# THS4524_Fully_Diff.net
KiCad netlist of a schematic drawn in Altium Designer
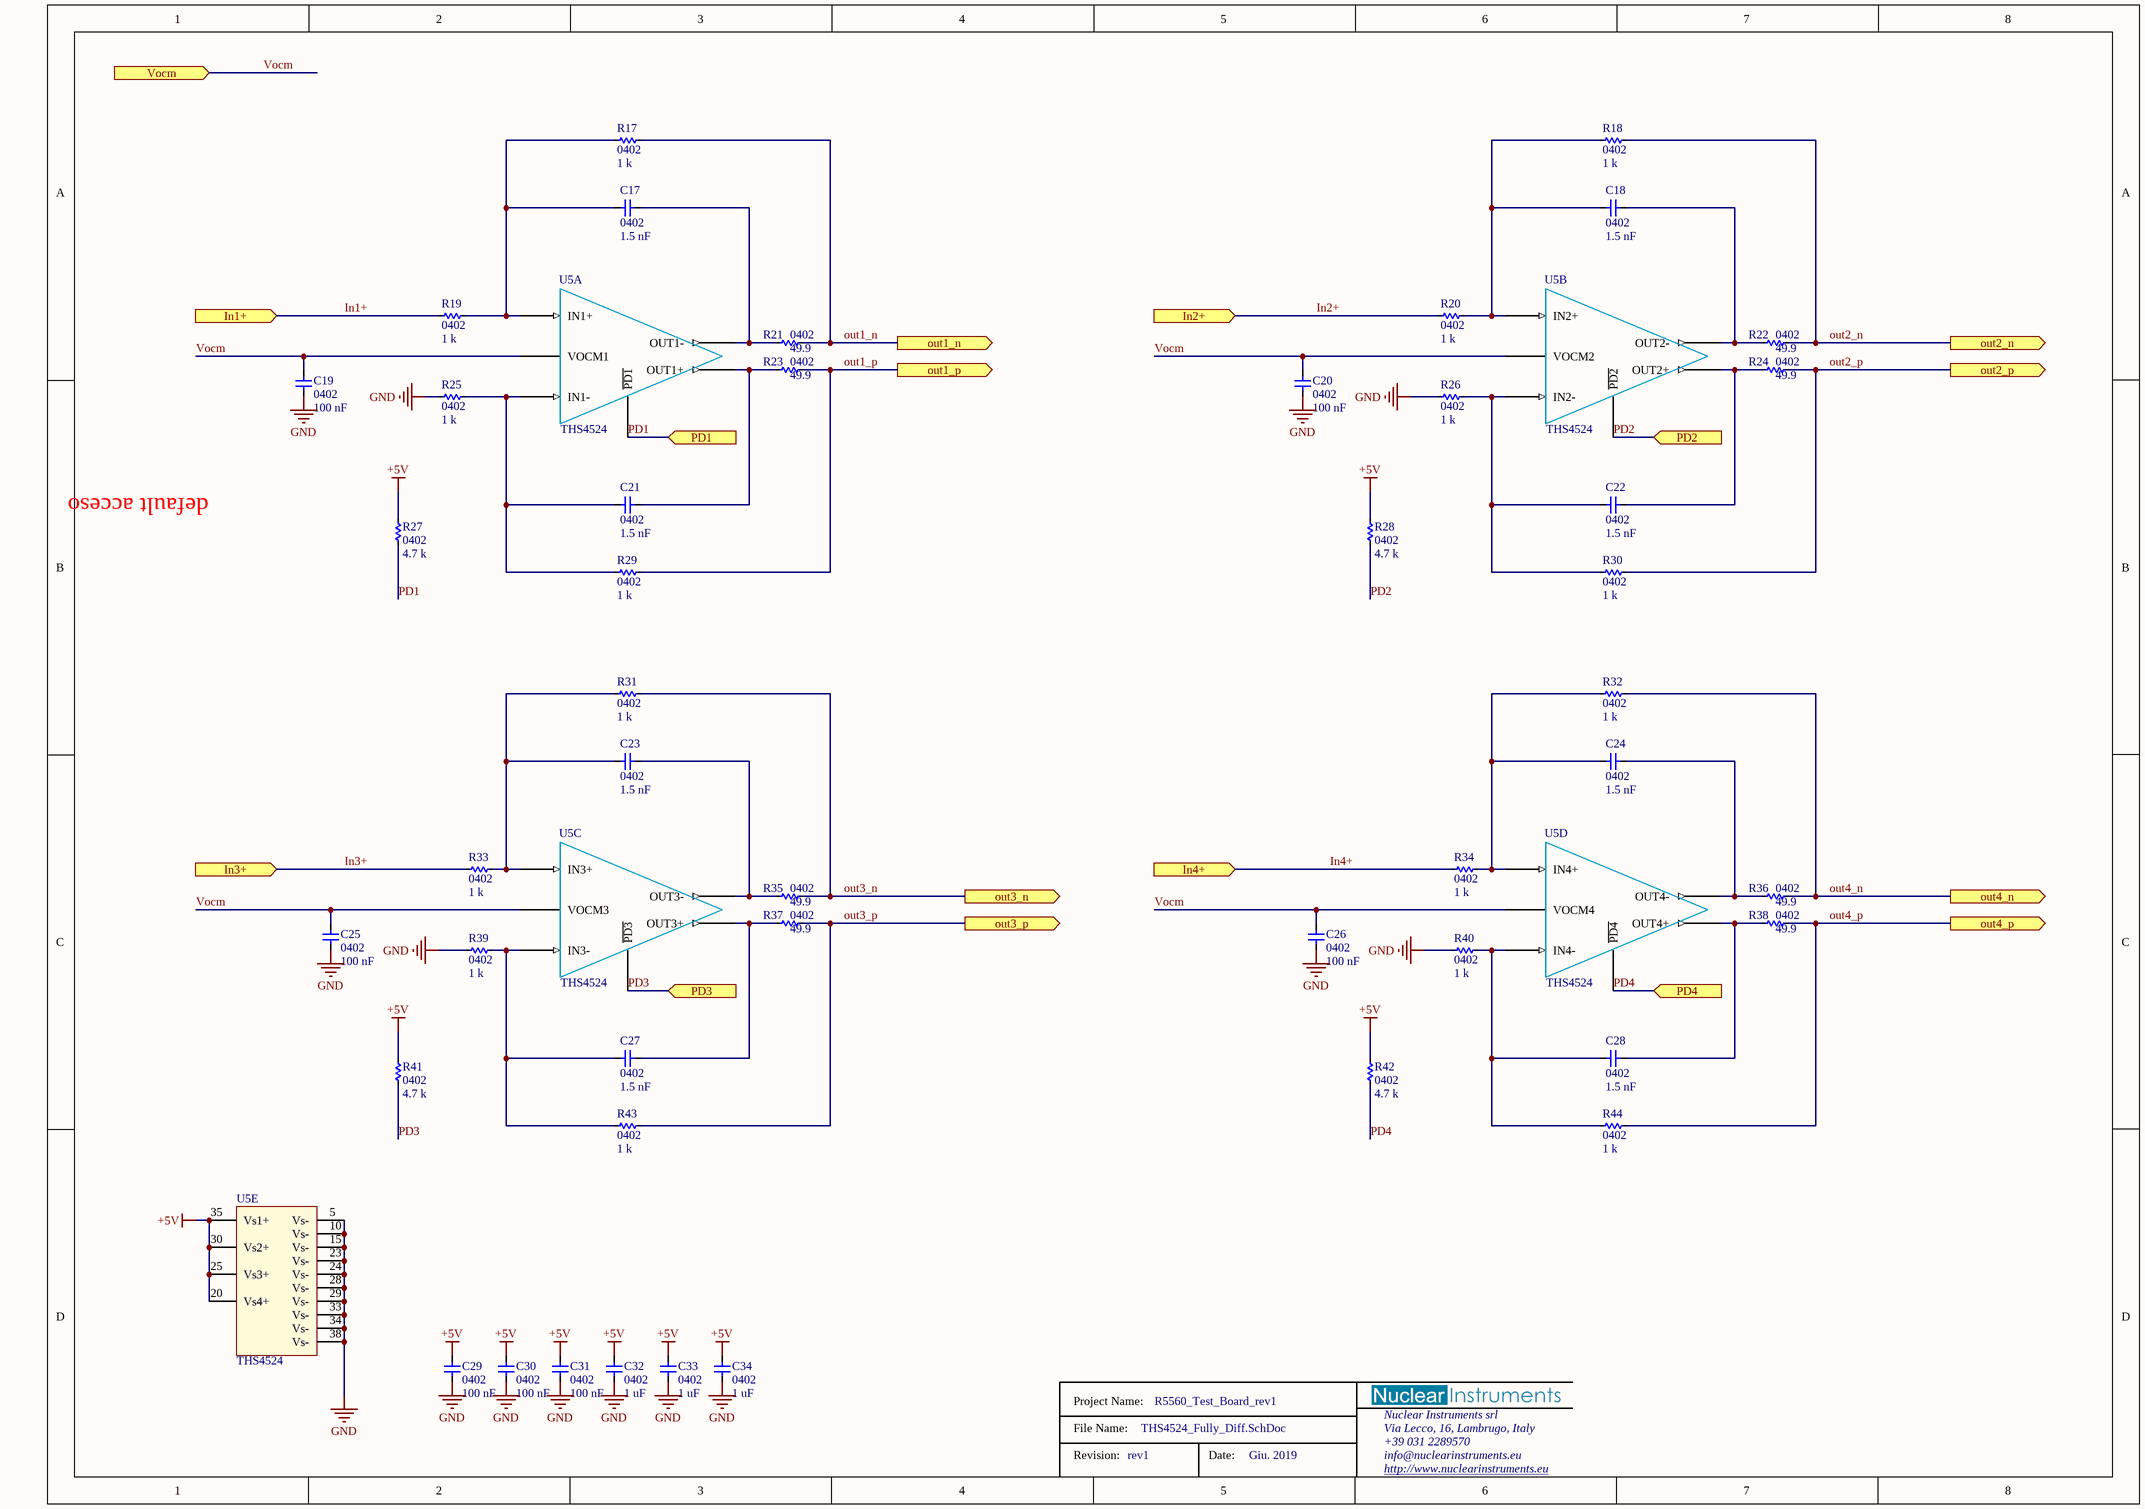
[diagram p0: THS4524_Fully_Diff.SchDoc]

(export (version "E")
  (design (tool "Eeschema 10.0.6"))
  (components
    (comp (ref "C17")
      (value "0402")
      (footprint "CAPCERSMD0402")
      (fields (field (name "ALTIUM_VALUE") "1.5 nF"))
      (libsource (lib "0402_Cap_Cer__SARAversion-23") (part "CAPCER0402_X7R_50V_1n5"))
    )
    (comp (ref "C18")
      (value "0402")
      (footprint "CAPCERSMD0402")
      (fields (field (name "ALTIUM_VALUE") "1.5 nF"))
      (libsource (lib "0402_Cap_Cer__SARAversion-23") (part "CAPCER0402_X7R_50V_1n5"))
    )
    (comp (ref "C19")
      (value "0402")
      (footprint "CAPCERSMD0402")
      (fields (field (name "ALTIUM_VALUE") "100 nF"))
      (libsource (lib "0402_Cap_Cer__SARAversion-23") (part "CAPCER0402_X7R_50V_100n"))
    )
    (comp (ref "C20")
      (value "0402")
      (footprint "CAPCERSMD0402")
      (fields (field (name "ALTIUM_VALUE") "100 nF"))
      (libsource (lib "0402_Cap_Cer__SARAversion-23") (part "CAPCER0402_X7R_50V_100n"))
    )
    (comp (ref "C21")
      (value "0402")
      (footprint "CAPCERSMD0402")
      (fields (field (name "ALTIUM_VALUE") "1.5 nF"))
      (libsource (lib "0402_Cap_Cer__SARAversion-23") (part "CAPCER0402_X7R_50V_1n5"))
    )
    (comp (ref "C22")
      (value "0402")
      (footprint "CAPCERSMD0402")
      (fields (field (name "ALTIUM_VALUE") "1.5 nF"))
      (libsource (lib "0402_Cap_Cer__SARAversion-23") (part "CAPCER0402_X7R_50V_1n5"))
    )
    (comp (ref "C23")
      (value "0402")
      (footprint "CAPCERSMD0402")
      (fields (field (name "ALTIUM_VALUE") "1.5 nF"))
      (libsource (lib "0402_Cap_Cer__SARAversion-23") (part "CAPCER0402_X7R_50V_1n5"))
    )
    (comp (ref "C24")
      (value "0402")
      (footprint "CAPCERSMD0402")
      (fields (field (name "ALTIUM_VALUE") "1.5 nF"))
      (libsource (lib "0402_Cap_Cer__SARAversion-23") (part "CAPCER0402_X7R_50V_1n5"))
    )
    (comp (ref "C25")
      (value "0402")
      (footprint "CAPCERSMD0402")
      (fields (field (name "ALTIUM_VALUE") "100 nF"))
      (libsource (lib "0402_Cap_Cer__SARAversion-23") (part "CAPCER0402_X7R_50V_100n"))
    )
    (comp (ref "C26")
      (value "0402")
      (footprint "CAPCERSMD0402")
      (fields (field (name "ALTIUM_VALUE") "100 nF"))
      (libsource (lib "0402_Cap_Cer__SARAversion-23") (part "CAPCER0402_X7R_50V_100n"))
    )
    (comp (ref "C27")
      (value "0402")
      (footprint "CAPCERSMD0402")
      (fields (field (name "ALTIUM_VALUE") "1.5 nF"))
      (libsource (lib "0402_Cap_Cer__SARAversion-23") (part "CAPCER0402_X7R_50V_1n5"))
    )
    (comp (ref "C28")
      (value "0402")
      (footprint "CAPCERSMD0402")
      (fields (field (name "ALTIUM_VALUE") "1.5 nF"))
      (libsource (lib "0402_Cap_Cer__SARAversion-23") (part "CAPCER0402_X7R_50V_1n5"))
    )
    (comp (ref "C29")
      (value "0402")
      (footprint "CAPCERSMD0402")
      (fields (field (name "ALTIUM_VALUE") "100 nF"))
      (libsource (lib "0402_Cap_Cer__SARAversion-23") (part "CAPCER0402_X7R_50V_100n"))
    )
    (comp (ref "C30")
      (value "0402")
      (footprint "CAPCERSMD0402")
      (fields (field (name "ALTIUM_VALUE") "100 nF"))
      (libsource (lib "0402_Cap_Cer__SARAversion-23") (part "CAPCER0402_X7R_50V_100n"))
    )
    (comp (ref "C31")
      (value "0402")
      (footprint "CAPCERSMD0402")
      (fields (field (name "ALTIUM_VALUE") "100 nF"))
      (libsource (lib "0402_Cap_Cer__SARAversion-23") (part "CAPCER0402_X7R_50V_100n"))
    )
    (comp (ref "C32")
      (value "0402")
      (footprint "CAPCERSMD0402")
      (fields (field (name "ALTIUM_VALUE") "1 uF"))
      (libsource (lib "0402_Cap_Cer__SARAversion-23") (part "CAPCER0402_X5R_10V_1u"))
    )
    (comp (ref "C33")
      (value "0402")
      (footprint "CAPCERSMD0402")
      (fields (field (name "ALTIUM_VALUE") "1 uF"))
      (libsource (lib "0402_Cap_Cer__SARAversion-23") (part "CAPCER0402_X5R_10V_1u"))
    )
    (comp (ref "C34")
      (value "0402")
      (footprint "CAPCERSMD0402")
      (fields (field (name "ALTIUM_VALUE") "1 uF"))
      (libsource (lib "0402_Cap_Cer__SARAversion-23") (part "CAPCER0402_X5R_10V_1u"))
    )
    (comp (ref "R17")
      (value "0402")
      (footprint "RESSMD0402")
      (fields (field (name "ALTIUM_VALUE") "1 k"))
      (libsource (lib "0402_Resistors__SARAversion-52") (part "RES0402-1k"))
    )
    (comp (ref "R18")
      (value "0402")
      (footprint "RESSMD0402")
      (fields (field (name "ALTIUM_VALUE") "1 k"))
      (libsource (lib "0402_Resistors__SARAversion-52") (part "RES0402-1k"))
    )
    (comp (ref "R19")
      (value "0402")
      (footprint "RESSMD0402")
      (fields (field (name "ALTIUM_VALUE") "1 k"))
      (libsource (lib "0402_Resistors__SARAversion-52") (part "RES0402-1k"))
    )
    (comp (ref "R20")
      (value "0402")
      (footprint "RESSMD0402")
      (fields (field (name "ALTIUM_VALUE") "1 k"))
      (libsource (lib "0402_Resistors__SARAversion-52") (part "RES0402-1k"))
    )
    (comp (ref "R21")
      (value "0402")
      (footprint "RESSMD0402")
      (fields (field (name "ALTIUM_VALUE") "49.9"))
      (libsource (lib "0402_Resistors__SARAversion-52") (part "RES0402-49R9"))
    )
    (comp (ref "R22")
      (value "0402")
      (footprint "RESSMD0402")
      (fields (field (name "ALTIUM_VALUE") "49.9"))
      (libsource (lib "0402_Resistors__SARAversion-52") (part "RES0402-49R9"))
    )
    (comp (ref "R23")
      (value "0402")
      (footprint "RESSMD0402")
      (fields (field (name "ALTIUM_VALUE") "49.9"))
      (libsource (lib "0402_Resistors__SARAversion-52") (part "RES0402-49R9"))
    )
    (comp (ref "R24")
      (value "0402")
      (footprint "RESSMD0402")
      (fields (field (name "ALTIUM_VALUE") "49.9"))
      (libsource (lib "0402_Resistors__SARAversion-52") (part "RES0402-49R9"))
    )
    (comp (ref "R25")
      (value "0402")
      (footprint "RESSMD0402")
      (fields (field (name "ALTIUM_VALUE") "1 k"))
      (libsource (lib "0402_Resistors__SARAversion-52") (part "RES0402-1k"))
    )
    (comp (ref "R26")
      (value "0402")
      (footprint "RESSMD0402")
      (fields (field (name "ALTIUM_VALUE") "1 k"))
      (libsource (lib "0402_Resistors__SARAversion-52") (part "RES0402-1k"))
    )
    (comp (ref "R27")
      (value "0402")
      (footprint "RESSMD0402")
      (fields (field (name "ALTIUM_VALUE") "4.7 k"))
      (libsource (lib "0402_Resistors__SARAversion-52") (part "RES0402-4k7"))
    )
    (comp (ref "R28")
      (value "0402")
      (footprint "RESSMD0402")
      (fields (field (name "ALTIUM_VALUE") "4.7 k"))
      (libsource (lib "0402_Resistors__SARAversion-52") (part "RES0402-4k7"))
    )
    (comp (ref "R29")
      (value "0402")
      (footprint "RESSMD0402")
      (fields (field (name "ALTIUM_VALUE") "1 k"))
      (libsource (lib "0402_Resistors__SARAversion-52") (part "RES0402-1k"))
    )
    (comp (ref "R30")
      (value "0402")
      (footprint "RESSMD0402")
      (fields (field (name "ALTIUM_VALUE") "1 k"))
      (libsource (lib "0402_Resistors__SARAversion-52") (part "RES0402-1k"))
    )
    (comp (ref "R31")
      (value "0402")
      (footprint "RESSMD0402")
      (fields (field (name "ALTIUM_VALUE") "1 k"))
      (libsource (lib "0402_Resistors__SARAversion-52") (part "RES0402-1k"))
    )
    (comp (ref "R32")
      (value "0402")
      (footprint "RESSMD0402")
      (fields (field (name "ALTIUM_VALUE") "1 k"))
      (libsource (lib "0402_Resistors__SARAversion-52") (part "RES0402-1k"))
    )
    (comp (ref "R33")
      (value "0402")
      (footprint "RESSMD0402")
      (fields (field (name "ALTIUM_VALUE") "1 k"))
      (libsource (lib "0402_Resistors__SARAversion-52") (part "RES0402-1k"))
    )
    (comp (ref "R34")
      (value "0402")
      (footprint "RESSMD0402")
      (fields (field (name "ALTIUM_VALUE") "1 k"))
      (libsource (lib "0402_Resistors__SARAversion-52") (part "RES0402-1k"))
    )
    (comp (ref "R35")
      (value "0402")
      (footprint "RESSMD0402")
      (fields (field (name "ALTIUM_VALUE") "49.9"))
      (libsource (lib "0402_Resistors__SARAversion-52") (part "RES0402-49R9"))
    )
    (comp (ref "R36")
      (value "0402")
      (footprint "RESSMD0402")
      (fields (field (name "ALTIUM_VALUE") "49.9"))
      (libsource (lib "0402_Resistors__SARAversion-52") (part "RES0402-49R9"))
    )
    (comp (ref "R37")
      (value "0402")
      (footprint "RESSMD0402")
      (fields (field (name "ALTIUM_VALUE") "49.9"))
      (libsource (lib "0402_Resistors__SARAversion-52") (part "RES0402-49R9"))
    )
    (comp (ref "R38")
      (value "0402")
      (footprint "RESSMD0402")
      (fields (field (name "ALTIUM_VALUE") "49.9"))
      (libsource (lib "0402_Resistors__SARAversion-52") (part "RES0402-49R9"))
    )
    (comp (ref "R39")
      (value "0402")
      (footprint "RESSMD0402")
      (fields (field (name "ALTIUM_VALUE") "1 k"))
      (libsource (lib "0402_Resistors__SARAversion-52") (part "RES0402-1k"))
    )
    (comp (ref "R40")
      (value "0402")
      (footprint "RESSMD0402")
      (fields (field (name "ALTIUM_VALUE") "1 k"))
      (libsource (lib "0402_Resistors__SARAversion-52") (part "RES0402-1k"))
    )
    (comp (ref "R41")
      (value "0402")
      (footprint "RESSMD0402")
      (fields (field (name "ALTIUM_VALUE") "4.7 k"))
      (libsource (lib "0402_Resistors__SARAversion-52") (part "RES0402-4k7"))
    )
    (comp (ref "R42")
      (value "0402")
      (footprint "RESSMD0402")
      (fields (field (name "ALTIUM_VALUE") "4.7 k"))
      (libsource (lib "0402_Resistors__SARAversion-52") (part "RES0402-4k7"))
    )
    (comp (ref "R43")
      (value "0402")
      (footprint "RESSMD0402")
      (fields (field (name "ALTIUM_VALUE") "1 k"))
      (libsource (lib "0402_Resistors__SARAversion-52") (part "RES0402-1k"))
    )
    (comp (ref "R44")
      (value "0402")
      (footprint "RESSMD0402")
      (fields (field (name "ALTIUM_VALUE") "1 k"))
      (libsource (lib "0402_Resistors__SARAversion-52") (part "RES0402-1k"))
    )
    (comp (ref "U5")
      (value "THS4524")
      (footprint "SOP38_P50W640L970H120")
      (libsource (lib "Fully_Differential__SARAversion-6") (part "THS4524IDBTR"))
    )
  )
  (nets
    (net (code "1") (name "+5V") (class "Default")
      (node (ref "C29") (pin "2") (pinfunction "2_2") (pintype "passive"))
      (node (ref "C30") (pin "2") (pinfunction "2_2") (pintype "passive"))
      (node (ref "C31") (pin "2") (pinfunction "2_2") (pintype "passive"))
      (node (ref "C32") (pin "2") (pinfunction "2_2") (pintype "passive"))
      (node (ref "C33") (pin "2") (pinfunction "2_2") (pintype "passive"))
      (node (ref "C34") (pin "2") (pinfunction "2_2") (pintype "passive"))
      (node (ref "R27") (pin "1") (pinfunction "1_1") (pintype "passive"))
      (node (ref "R28") (pin "1") (pinfunction "1_1") (pintype "passive"))
      (node (ref "R41") (pin "1") (pinfunction "1_1") (pintype "passive"))
      (node (ref "R42") (pin "1") (pinfunction "1_1") (pintype "passive"))
      (node (ref "U5") (pin "20") (pinfunction "Vs4+_20") (pintype "passive"))
      (node (ref "U5") (pin "25") (pinfunction "Vs3+_25") (pintype "passive"))
      (node (ref "U5") (pin "30") (pinfunction "Vs2+_30") (pintype "passive"))
      (node (ref "U5") (pin "35") (pinfunction "Vs1+_35") (pintype "passive"))
    )
    (net (code "2") (name "/In1+") (class "Default")
      (node (ref "R19") (pin "1") (pinfunction "1_1") (pintype "passive"))
    )
    (net (code "3") (name "/In2+") (class "Default")
      (node (ref "R20") (pin "1") (pinfunction "1_1") (pintype "passive"))
    )
    (net (code "4") (name "/In3+") (class "Default")
      (node (ref "R33") (pin "1") (pinfunction "1_1") (pintype "passive"))
    )
    (net (code "5") (name "/In4+") (class "Default")
      (node (ref "R34") (pin "1") (pinfunction "1_1") (pintype "passive"))
    )
    (net (code "6") (name "/PD1") (class "Default")
      (node (ref "R27") (pin "2") (pinfunction "2_2") (pintype "passive"))
      (node (ref "U5") (pin "1") (pinfunction "~{PD1}_1") (pintype "passive"))
    )
    (net (code "7") (name "/PD2") (class "Default")
      (node (ref "R28") (pin "2") (pinfunction "2_2") (pintype "passive"))
      (node (ref "U5") (pin "6") (pinfunction "~{PD2}_6") (pintype "passive"))
    )
    (net (code "8") (name "/PD3") (class "Default")
      (node (ref "R41") (pin "2") (pinfunction "2_2") (pintype "passive"))
      (node (ref "U5") (pin "11") (pinfunction "~{PD3}_11") (pintype "passive"))
    )
    (net (code "9") (name "/PD4") (class "Default")
      (node (ref "R42") (pin "2") (pinfunction "2_2") (pintype "passive"))
      (node (ref "U5") (pin "16") (pinfunction "~{PD4}_16") (pintype "passive"))
    )
    (net (code "10") (name "/Vocm") (class "Default")
      (node (ref "C19") (pin "2") (pinfunction "2_2") (pintype "passive"))
      (node (ref "C20") (pin "2") (pinfunction "2_2") (pintype "passive"))
      (node (ref "C25") (pin "2") (pinfunction "2_2") (pintype "passive"))
      (node (ref "C26") (pin "2") (pinfunction "2_2") (pintype "passive"))
      (node (ref "U5") (pin "14") (pinfunction "VOCM3_14") (pintype "passive"))
      (node (ref "U5") (pin "19") (pinfunction "VOCM4_19") (pintype "passive"))
      (node (ref "U5") (pin "4") (pinfunction "VOCM1_4") (pintype "passive"))
      (node (ref "U5") (pin "9") (pinfunction "VOCM2_9") (pintype "passive"))
    )
    (net (code "11") (name "/out1_n") (class "Default")
      (node (ref "R17") (pin "2") (pinfunction "2_2") (pintype "passive"))
      (node (ref "R21") (pin "2") (pinfunction "2_2") (pintype "passive"))
    )
    (net (code "12") (name "/out1_p") (class "Default")
      (node (ref "R23") (pin "2") (pinfunction "2_2") (pintype "passive"))
      (node (ref "R29") (pin "2") (pinfunction "2_2") (pintype "passive"))
    )
    (net (code "13") (name "/out2_n") (class "Default")
      (node (ref "R18") (pin "2") (pinfunction "2_2") (pintype "passive"))
      (node (ref "R22") (pin "2") (pinfunction "2_2") (pintype "passive"))
    )
    (net (code "14") (name "/out2_p") (class "Default")
      (node (ref "R24") (pin "2") (pinfunction "2_2") (pintype "passive"))
      (node (ref "R30") (pin "2") (pinfunction "2_2") (pintype "passive"))
    )
    (net (code "15") (name "/out3_n") (class "Default")
      (node (ref "R31") (pin "2") (pinfunction "2_2") (pintype "passive"))
      (node (ref "R35") (pin "2") (pinfunction "2_2") (pintype "passive"))
    )
    (net (code "16") (name "/out3_p") (class "Default")
      (node (ref "R37") (pin "2") (pinfunction "2_2") (pintype "passive"))
      (node (ref "R43") (pin "2") (pinfunction "2_2") (pintype "passive"))
    )
    (net (code "17") (name "/out4_n") (class "Default")
      (node (ref "R32") (pin "2") (pinfunction "2_2") (pintype "passive"))
      (node (ref "R36") (pin "2") (pinfunction "2_2") (pintype "passive"))
    )
    (net (code "18") (name "/out4_p") (class "Default")
      (node (ref "R38") (pin "2") (pinfunction "2_2") (pintype "passive"))
      (node (ref "R44") (pin "2") (pinfunction "2_2") (pintype "passive"))
    )
    (net (code "19") (name "GND") (class "Default")
      (node (ref "C19") (pin "1") (pinfunction "1_1") (pintype "passive"))
      (node (ref "C20") (pin "1") (pinfunction "1_1") (pintype "passive"))
      (node (ref "C25") (pin "1") (pinfunction "1_1") (pintype "passive"))
      (node (ref "C26") (pin "1") (pinfunction "1_1") (pintype "passive"))
      (node (ref "C29") (pin "1") (pinfunction "1_1") (pintype "passive"))
      (node (ref "C30") (pin "1") (pinfunction "1_1") (pintype "passive"))
      (node (ref "C31") (pin "1") (pinfunction "1_1") (pintype "passive"))
      (node (ref "C32") (pin "1") (pinfunction "1_1") (pintype "passive"))
      (node (ref "C33") (pin "1") (pinfunction "1_1") (pintype "passive"))
      (node (ref "C34") (pin "1") (pinfunction "1_1") (pintype "passive"))
      (node (ref "R25") (pin "1") (pinfunction "1_1") (pintype "passive"))
      (node (ref "R26") (pin "1") (pinfunction "1_1") (pintype "passive"))
      (node (ref "R39") (pin "1") (pinfunction "1_1") (pintype "passive"))
      (node (ref "R40") (pin "1") (pinfunction "1_1") (pintype "passive"))
      (node (ref "U5") (pin "10") (pinfunction "Vs-_10") (pintype "passive"))
      (node (ref "U5") (pin "15") (pinfunction "Vs-_15") (pintype "passive"))
      (node (ref "U5") (pin "23") (pinfunction "Vs-_23") (pintype "passive"))
      (node (ref "U5") (pin "24") (pinfunction "Vs-_24") (pintype "passive"))
      (node (ref "U5") (pin "28") (pinfunction "Vs-_28") (pintype "passive"))
      (node (ref "U5") (pin "29") (pinfunction "Vs-_29") (pintype "passive"))
      (node (ref "U5") (pin "33") (pinfunction "Vs-_33") (pintype "passive"))
      (node (ref "U5") (pin "34") (pinfunction "Vs-_34") (pintype "passive"))
      (node (ref "U5") (pin "38") (pinfunction "Vs-_38") (pintype "passive"))
      (node (ref "U5") (pin "5") (pinfunction "Vs-_5") (pintype "passive"))
    )
    (net (code "20") (name "Net-(U5A-IN1+)") (class "Default")
      (node (ref "C17") (pin "2") (pinfunction "2_2") (pintype "passive"))
      (node (ref "R17") (pin "1") (pinfunction "1_1") (pintype "passive"))
      (node (ref "R19") (pin "2") (pinfunction "2_2") (pintype "passive"))
      (node (ref "U5") (pin "2") (pinfunction "IN1+_2") (pintype "input"))
    )
    (net (code "21") (name "Net-(U5A-IN1-)") (class "Default")
      (node (ref "C21") (pin "2") (pinfunction "2_2") (pintype "passive"))
      (node (ref "R25") (pin "2") (pinfunction "2_2") (pintype "passive"))
      (node (ref "R29") (pin "1") (pinfunction "1_1") (pintype "passive"))
      (node (ref "U5") (pin "3") (pinfunction "IN1-_3") (pintype "input"))
    )
    (net (code "22") (name "Net-(U5A-OUT1+)") (class "Default")
      (node (ref "C21") (pin "1") (pinfunction "1_1") (pintype "passive"))
      (node (ref "R23") (pin "1") (pinfunction "1_1") (pintype "passive"))
      (node (ref "U5") (pin "36") (pinfunction "OUT1+_36") (pintype "output"))
    )
    (net (code "23") (name "Net-(U5A-OUT1-)") (class "Default")
      (node (ref "C17") (pin "1") (pinfunction "1_1") (pintype "passive"))
      (node (ref "R21") (pin "1") (pinfunction "1_1") (pintype "passive"))
      (node (ref "U5") (pin "37") (pinfunction "OUT1-_37") (pintype "output"))
    )
    (net (code "24") (name "Net-(U5B-IN2+)") (class "Default")
      (node (ref "C18") (pin "2") (pinfunction "2_2") (pintype "passive"))
      (node (ref "R18") (pin "1") (pinfunction "1_1") (pintype "passive"))
      (node (ref "R20") (pin "2") (pinfunction "2_2") (pintype "passive"))
      (node (ref "U5") (pin "7") (pinfunction "IN2+_7") (pintype "input"))
    )
    (net (code "25") (name "Net-(U5B-IN2-)") (class "Default")
      (node (ref "C22") (pin "2") (pinfunction "2_2") (pintype "passive"))
      (node (ref "R26") (pin "2") (pinfunction "2_2") (pintype "passive"))
      (node (ref "R30") (pin "1") (pinfunction "1_1") (pintype "passive"))
      (node (ref "U5") (pin "8") (pinfunction "IN2-_8") (pintype "input"))
    )
    (net (code "26") (name "Net-(U5B-OUT2+)") (class "Default")
      (node (ref "C22") (pin "1") (pinfunction "1_1") (pintype "passive"))
      (node (ref "R24") (pin "1") (pinfunction "1_1") (pintype "passive"))
      (node (ref "U5") (pin "31") (pinfunction "OUT2+_31") (pintype "output"))
    )
    (net (code "27") (name "Net-(U5B-OUT2-)") (class "Default")
      (node (ref "C18") (pin "1") (pinfunction "1_1") (pintype "passive"))
      (node (ref "R22") (pin "1") (pinfunction "1_1") (pintype "passive"))
      (node (ref "U5") (pin "32") (pinfunction "OUT2-_32") (pintype "output"))
    )
    (net (code "28") (name "Net-(U5C-IN3+)") (class "Default")
      (node (ref "C23") (pin "2") (pinfunction "2_2") (pintype "passive"))
      (node (ref "R31") (pin "1") (pinfunction "1_1") (pintype "passive"))
      (node (ref "R33") (pin "2") (pinfunction "2_2") (pintype "passive"))
      (node (ref "U5") (pin "12") (pinfunction "IN3+_12") (pintype "input"))
    )
    (net (code "29") (name "Net-(U5C-IN3-)") (class "Default")
      (node (ref "C27") (pin "2") (pinfunction "2_2") (pintype "passive"))
      (node (ref "R39") (pin "2") (pinfunction "2_2") (pintype "passive"))
      (node (ref "R43") (pin "1") (pinfunction "1_1") (pintype "passive"))
      (node (ref "U5") (pin "13") (pinfunction "IN3-_13") (pintype "input"))
    )
    (net (code "30") (name "Net-(U5C-OUT3+)") (class "Default")
      (node (ref "C27") (pin "1") (pinfunction "1_1") (pintype "passive"))
      (node (ref "R37") (pin "1") (pinfunction "1_1") (pintype "passive"))
      (node (ref "U5") (pin "26") (pinfunction "OUT3+_26") (pintype "output"))
    )
    (net (code "31") (name "Net-(U5C-OUT3-)") (class "Default")
      (node (ref "C23") (pin "1") (pinfunction "1_1") (pintype "passive"))
      (node (ref "R35") (pin "1") (pinfunction "1_1") (pintype "passive"))
      (node (ref "U5") (pin "27") (pinfunction "OUT3-_27") (pintype "output"))
    )
    (net (code "32") (name "Net-(U5D-IN4+)") (class "Default")
      (node (ref "C24") (pin "2") (pinfunction "2_2") (pintype "passive"))
      (node (ref "R32") (pin "1") (pinfunction "1_1") (pintype "passive"))
      (node (ref "R34") (pin "2") (pinfunction "2_2") (pintype "passive"))
      (node (ref "U5") (pin "17") (pinfunction "IN4+_17") (pintype "input"))
    )
    (net (code "33") (name "Net-(U5D-IN4-)") (class "Default")
      (node (ref "C28") (pin "2") (pinfunction "2_2") (pintype "passive"))
      (node (ref "R40") (pin "2") (pinfunction "2_2") (pintype "passive"))
      (node (ref "R44") (pin "1") (pinfunction "1_1") (pintype "passive"))
      (node (ref "U5") (pin "18") (pinfunction "IN4-_18") (pintype "input"))
    )
    (net (code "34") (name "Net-(U5D-OUT4+)") (class "Default")
      (node (ref "C28") (pin "1") (pinfunction "1_1") (pintype "passive"))
      (node (ref "R38") (pin "1") (pinfunction "1_1") (pintype "passive"))
      (node (ref "U5") (pin "21") (pinfunction "OUT4+_21") (pintype "output"))
    )
    (net (code "35") (name "Net-(U5D-OUT4-)") (class "Default")
      (node (ref "C24") (pin "1") (pinfunction "1_1") (pintype "passive"))
      (node (ref "R36") (pin "1") (pinfunction "1_1") (pintype "passive"))
      (node (ref "U5") (pin "22") (pinfunction "OUT4-_22") (pintype "output"))
    )
  )
)
